# illumination_module.net
KiCad netlist of a schematic drawn in EAGLE
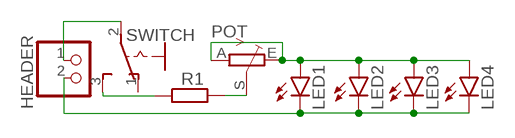
[diagram p0: schematic, sheet 1]

(export (version "E")
  (design (tool "Eeschema 10.0.6"))
  (components
    (comp (ref "HEADER")
      (value "PINHD-1X2/90")
      (footprint "eagle-import:1X02_90")
      (libsource (lib "eagle-import") (part "PINHD-1X2/90"))
    )
    (comp (ref "LED1")
      (value "LED5MM")
      (footprint "eagle-import:LED5MM")
      (libsource (lib "eagle-import") (part "LED5MM"))
    )
    (comp (ref "LED2")
      (value "LED5MM")
      (footprint "eagle-import:LED5MM")
      (libsource (lib "eagle-import") (part "LED5MM"))
    )
    (comp (ref "LED3")
      (value "LED5MM")
      (footprint "eagle-import:LED5MM")
      (libsource (lib "eagle-import") (part "LED5MM"))
    )
    (comp (ref "LED4")
      (value "LED5MM")
      (footprint "eagle-import:LED5MM")
      (libsource (lib "eagle-import") (part "LED5MM"))
    )
    (comp (ref "POT")
      (value "TRIM_EU-CA6H")
      (footprint "eagle-import:CA6H")
      (libsource (lib "eagle-import") (part "TRIM_EU-CA6H"))
    )
    (comp (ref "R1")
      (value "R-EU_0207/10")
      (footprint "eagle-import:0207_10")
      (libsource (lib "eagle-import") (part "R-EU_0207/10"))
    )
    (comp (ref "SWITCH")
      (value "255SB")
      (footprint "eagle-import:255SB")
      (libsource (lib "eagle-import") (part "255SB"))
    )
  )
  (nets
    (net (code "1") (name "Net-(LED1-C)") (class "Default")
      (node (ref "HEADER") (pin "2") (pinfunction "2_2") (pintype "passive"))
      (node (ref "LED1") (pin "K") (pinfunction "C_K") (pintype "passive"))
      (node (ref "LED2") (pin "K") (pinfunction "C_K") (pintype "passive"))
      (node (ref "LED3") (pin "K") (pinfunction "C_K") (pintype "passive"))
      (node (ref "LED4") (pin "K") (pinfunction "C_K") (pintype "passive"))
    )
    (net (code "2") (name "Net-(LED1-PadA)") (class "Default")
      (node (ref "LED1") (pin "A") (pinfunction "A_A") (pintype "passive"))
      (node (ref "LED2") (pin "A") (pinfunction "A_A") (pintype "passive"))
      (node (ref "LED3") (pin "A") (pinfunction "A_A") (pintype "passive"))
      (node (ref "LED4") (pin "A") (pinfunction "A_A") (pintype "passive"))
      (node (ref "POT") (pin "A") (pinfunction "A_A") (pintype "passive"))
      (node (ref "POT") (pin "E") (pinfunction "E_E") (pintype "passive"))
    )
    (net (code "3") (name "Net-(POT-PadS)") (class "Default")
      (node (ref "POT") (pin "S") (pinfunction "S_S") (pintype "passive"))
      (node (ref "R1") (pin "2") (pinfunction "2_2") (pintype "passive"))
    )
    (net (code "4") (name "Net-(SWITCH-P)") (class "Default")
      (node (ref "HEADER") (pin "1") (pinfunction "1_1") (pintype "passive"))
      (node (ref "SWITCH") (pin "2") (pinfunction "P_2") (pintype "passive"))
    )
    (net (code "5") (name "Net-(SWITCH-S)") (class "Default")
      (node (ref "R1") (pin "1") (pinfunction "1_1") (pintype "passive"))
      (node (ref "SWITCH") (pin "3") (pinfunction "S_3") (pintype "passive"))
    )
    (net (code "6") (name "unconnected-(SWITCH-O-Pad1)") (class "Default")
      (node (ref "SWITCH") (pin "1") (pinfunction "O_1") (pintype "passive"))
    )
  )
)
